# Power_Supply.net
KiCad netlist of a schematic drawn in Altium Designer
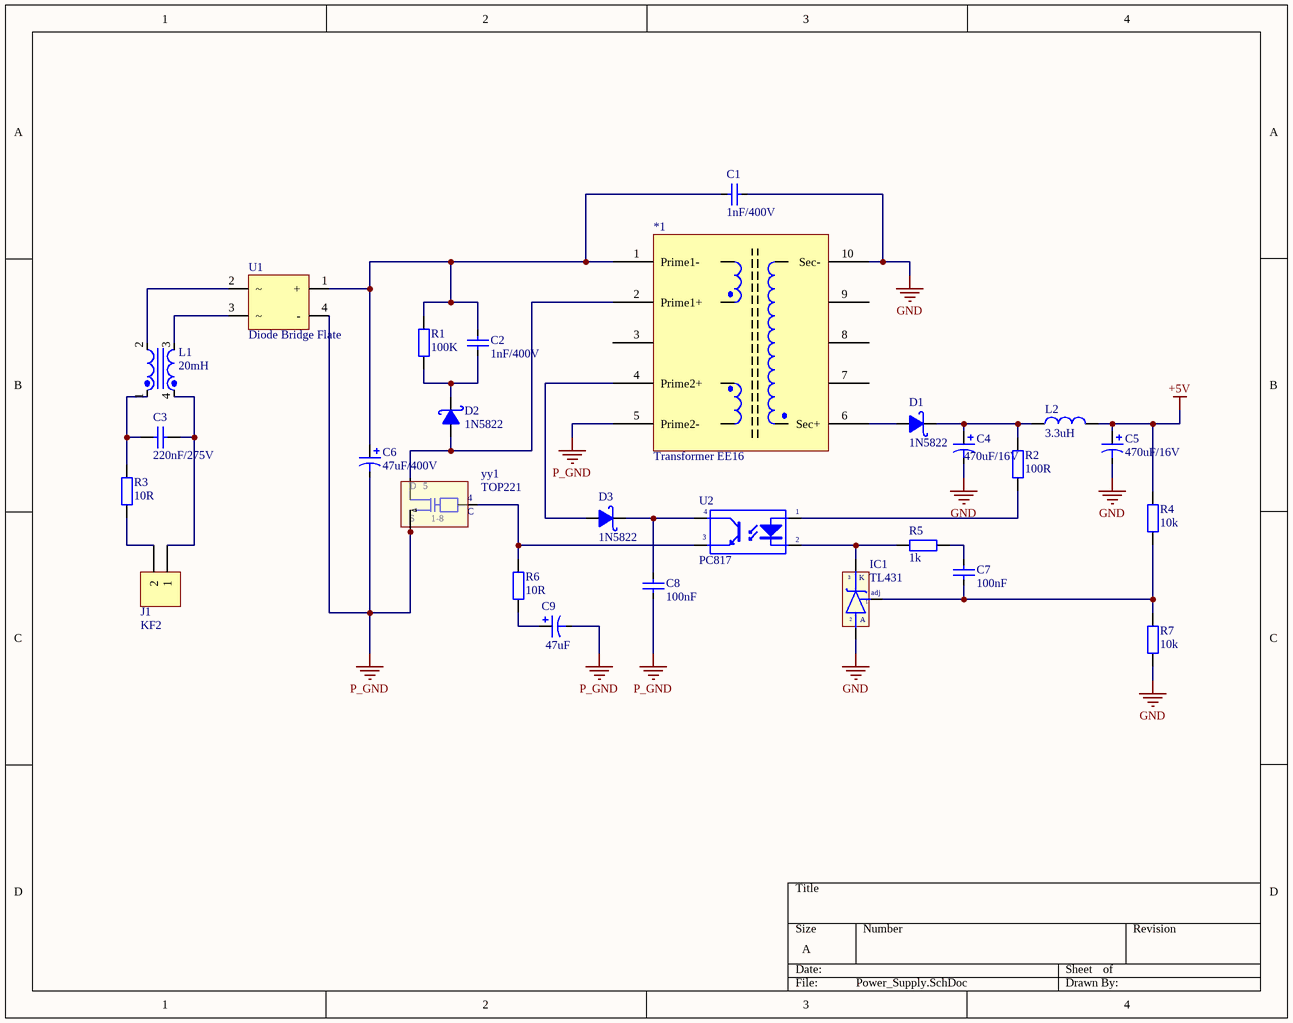
[diagram p0: Power_Supply.SchDoc]

(export (version "E")
  (design (tool "Eeschema 10.0.6"))
  (components
    (comp (ref "*1")
      (value "Transformer EE16")
      (footprint "Transformer SW")
      (libsource (lib "My Library") (part "Transformer EE16"))
    )
    (comp (ref "C1")
      (value "1nF/400V")
      (footprint "103/2KV")
      (description "Capacitor Ceramic 2KV")
      (fields (field (name "PUBLISHER") "Altium Limited"))
      (libsource (lib "My Library") (part "Cap2KV"))
    )
    (comp (ref "C2")
      (value "1nF/400V")
      (footprint "103/2KV")
      (description "Capacitor Ceramic 2KV")
      (fields (field (name "PUBLISHER") "Altium Limited"))
      (libsource (lib "My Library") (part "Cap2KV"))
    )
    (comp (ref "C3")
      (value "220nF/275V")
      (footprint "CN3")
      (description "Capacitor")
      (fields (field (name "Comment") "Capacitor Ceramic") (field (name "PUBLISHER") "Altium Limited"))
      (libsource (lib "My Library") (part "CapCeramic"))
    )
    (comp (ref "C4")
      (value "470uF/16V")
      (footprint "C5mm")
      (description "Polarized Capacitor (Axial)")
      (fields (field (name "PUBLISHER") "Altium Limited"))
      (libsource (lib "My Library") (part "Cap Pol"))
    )
    (comp (ref "C5")
      (value "470uF/16V")
      (footprint "C5mm")
      (description "Polarized Capacitor (Axial)")
      (fields (field (name "PUBLISHER") "Altium Limited"))
      (libsource (lib "My Library") (part "Cap Pol"))
    )
    (comp (ref "C6")
      (value "47uF/400V")
      (footprint "C10mm")
      (description "Polarized Capacitor (Axial)")
      (fields (field (name "PUBLISHER") "Altium Limited"))
      (libsource (lib "My Library") (part "Cap Pol"))
    )
    (comp (ref "C7")
      (value "100nF")
      (footprint "103/2KV")
      (description "Capacitor Ceramic 2KV")
      (fields (field (name "PUBLISHER") "Altium Limited"))
      (libsource (lib "My Library") (part "Cap2KV"))
    )
    (comp (ref "C8")
      (value "100nF")
      (footprint "103/2KV")
      (description "Capacitor Ceramic 2KV")
      (fields (field (name "PUBLISHER") "Altium Limited"))
      (libsource (lib "My Library") (part "Cap2KV"))
    )
    (comp (ref "C9")
      (value "47uF")
      (footprint "C3MM")
      (description "Polarized Capacitor (Axial)")
      (fields (field (name "PUBLISHER") "Altium Limited"))
      (libsource (lib "My Library") (part "Cap Pol"))
    )
    (comp (ref "D1")
      (value "1N5822")
      (footprint "DO-214AC(SMA)")
      (description "Schottky Rectifiers")
      (libsource (lib "My Library") (part "1N5822"))
    )
    (comp (ref "D2")
      (value "1N5822")
      (footprint "DO-214AC(SMA)")
      (description "Schottky Rectifiers")
      (libsource (lib "My Library") (part "1N5822"))
    )
    (comp (ref "D3")
      (value "1N5822")
      (footprint "DO-214AC(SMA)")
      (description "Schottky Rectifiers")
      (libsource (lib "My Library") (part "1N5822"))
    )
    (comp (ref "IC1")
      (value "TL431")
      (footprint "qto-92")
      (description "Programmable Shunt Regulator")
      (libsource (lib "My Library") (part "TL431"))
    )
    (comp (ref "J1")
      (value "KF2")
      (footprint "KF2-5.08")
      (fields
        (field (name "MANUFACTURER") "Würth Elektronik eiSos GmbH")
        (field (name "PARTNO") "691103110002")
        (field (name "CREATED BY") "Karrer Zheng")
      )
      (libsource (lib "My Library") (part "KF2"))
    )
    (comp (ref "L1")
      (value "20mH")
      (footprint "InductorFilter")
      (description "Inductor")
      (fields (field (name "DESIGNED BY") "VanDungEvn"))
      (libsource (lib "My Library") (part "L fiter"))
    )
    (comp (ref "L2")
      (value "3.3uH")
      (footprint "My Library:L-SMD-M-12x10")
      (description "Inductor")
      (libsource (lib "My Library") (part "Inductor"))
    )
    (comp (ref "R1")
      (value "100K")
      (footprint "RES-1WD")
      (description "Resistor SMD")
      (libsource (lib "My Library") (part "RM"))
    )
    (comp (ref "R2")
      (value "100R")
      (footprint "SM-0805")
      (description "Resistor SMD")
      (libsource (lib "My Library") (part "RM"))
    )
    (comp (ref "R3")
      (value "10R")
      (footprint "RES-1WD")
      (description "Resistor SMD")
      (libsource (lib "My Library") (part "RM"))
    )
    (comp (ref "R4")
      (value "10k")
      (footprint "SM-0805")
      (description "Resistor SMD")
      (libsource (lib "My Library") (part "RM"))
    )
    (comp (ref "R5")
      (value "1k")
      (footprint "SM-0805")
      (description "Resistor SMD")
      (libsource (lib "My Library") (part "RM"))
    )
    (comp (ref "R6")
      (value "10R")
      (footprint "SM-0805")
      (description "Resistor SMD")
      (libsource (lib "My Library") (part "RM"))
    )
    (comp (ref "R7")
      (value "10k")
      (footprint "SM-0805")
      (description "Resistor SMD")
      (libsource (lib "My Library") (part "RM"))
    )
    (comp (ref "U1")
      (value "Diode Bridge Flate")
      (footprint "DB207S")
      (description "Diode Bridge")
      (libsource (lib "My Library") (part "Diode Bridge Flate"))
    )
    (comp (ref "U2")
      (value "PC817")
      (footprint "DIP4/W0.3")
      (description "Single Opto")
      (libsource (lib "My Library") (part "PC817"))
    )
    (comp (ref "yy1")
      (value "TOP221")
      (footprint "DIP8/W0.3")
      (description "Family Three-terminal Off-line PWM Switch")
      (libsource (lib "My Library") (part "TOP221-7PG"))
    )
  )
  (nets
    (net (code "1") (name "+5V") (class "Default")
      (node (ref "C5") (pin "1") (pinfunction "1_1") (pintype "passive"))
      (node (ref "L2") (pin "2") (pinfunction "2_2") (pintype "passive"))
      (node (ref "R4") (pin "1") (pinfunction "1_1") (pintype "passive"))
    )
    (net (code "2") (name "GND") (class "Default")
      (node (ref "*1") (pin "10") (pinfunction "Sec-_10") (pintype "passive"))
      (node (ref "C1") (pin "1") (pinfunction "1_1") (pintype "passive"))
      (node (ref "C4") (pin "2") (pinfunction "2_2") (pintype "passive"))
      (node (ref "C5") (pin "2") (pinfunction "2_2") (pintype "passive"))
      (node (ref "IC1") (pin "2") (pinfunction "A_2") (pintype "passive"))
      (node (ref "R7") (pin "2") (pinfunction "2_2") (pintype "passive"))
    )
    (net (code "3") (name "Net-(*1-Prime1+)") (class "Default")
      (node (ref "*1") (pin "2") (pinfunction "Prime1+_2") (pintype "passive"))
      (node (ref "D2") (pin "1") (pinfunction "A_1") (pintype "passive"))
      (node (ref "yy1") (pin "5") (pinfunction "D_5") (pintype "passive"))
    )
    (net (code "4") (name "Net-(*1-Prime1-)") (class "Default")
      (node (ref "*1") (pin "1") (pinfunction "Prime1-_1") (pintype "passive"))
      (node (ref "C1") (pin "2") (pinfunction "2_2") (pintype "passive"))
      (node (ref "C2") (pin "2") (pinfunction "2_2") (pintype "passive"))
      (node (ref "C6") (pin "1") (pinfunction "1_1") (pintype "passive"))
      (node (ref "R1") (pin "2") (pinfunction "2_2") (pintype "passive"))
      (node (ref "U1") (pin "1") (pinfunction "+_1") (pintype "passive"))
    )
    (net (code "5") (name "Net-(*1-Prime2+)") (class "Default")
      (node (ref "*1") (pin "4") (pinfunction "Prime2+_4") (pintype "passive"))
      (node (ref "D3") (pin "1") (pinfunction "A_1") (pintype "passive"))
    )
    (net (code "6") (name "Net-(*1-Sec+)") (class "Default")
      (node (ref "*1") (pin "6") (pinfunction "Sec+_6") (pintype "passive"))
      (node (ref "D1") (pin "1") (pinfunction "A_1") (pintype "passive"))
    )
    (net (code "7") (name "Net-(C3-Pad1)") (class "Default")
      (node (ref "C3") (pin "1") (pinfunction "1_1") (pintype "passive"))
      (node (ref "L1") (pin "1") (pintype "passive"))
      (node (ref "R3") (pin "2") (pinfunction "2_2") (pintype "passive"))
    )
    (net (code "8") (name "Net-(C3-Pad2)") (class "Default")
      (node (ref "C3") (pin "2") (pinfunction "2_2") (pintype "passive"))
      (node (ref "J1") (pin "1") (pinfunction "1_1") (pintype "passive"))
      (node (ref "L1") (pin "4") (pintype "passive"))
    )
    (net (code "9") (name "Net-(C7-Pad2)") (class "Default")
      (node (ref "C7") (pin "2") (pinfunction "2_2") (pintype "passive"))
      (node (ref "R5") (pin "1") (pinfunction "1_1") (pintype "passive"))
    )
    (net (code "10") (name "Net-(C9-Pad1)") (class "Default")
      (node (ref "C9") (pin "1") (pinfunction "1_1") (pintype "passive"))
      (node (ref "R6") (pin "1") (pinfunction "1_1") (pintype "passive"))
    )
    (net (code "11") (name "Net-(D1-K)") (class "Default")
      (node (ref "C4") (pin "1") (pinfunction "1_1") (pintype "passive"))
      (node (ref "D1") (pin "2") (pinfunction "K_2") (pintype "passive"))
      (node (ref "L2") (pin "1") (pinfunction "1_1") (pintype "passive"))
      (node (ref "R2") (pin "2") (pinfunction "2_2") (pintype "passive"))
    )
    (net (code "12") (name "Net-(D2-K)") (class "Default")
      (node (ref "C2") (pin "1") (pinfunction "1_1") (pintype "passive"))
      (node (ref "D2") (pin "2") (pinfunction "K_2") (pintype "passive"))
      (node (ref "R1") (pin "1") (pinfunction "1_1") (pintype "passive"))
    )
    (net (code "13") (name "Net-(D3-K)") (class "Default")
      (node (ref "C8") (pin "2") (pinfunction "2_2") (pintype "passive"))
      (node (ref "D3") (pin "2") (pinfunction "K_2") (pintype "passive"))
      (node (ref "U2") (pin "4") (pinfunction "C_4") (pintype "passive"))
    )
    (net (code "14") (name "Net-(IC1-K)") (class "Default")
      (node (ref "IC1") (pin "3") (pinfunction "K_3") (pintype "passive"))
      (node (ref "R5") (pin "2") (pinfunction "2_2") (pintype "passive"))
      (node (ref "U2") (pin "2") (pinfunction "K_2") (pintype "passive"))
    )
    (net (code "15") (name "Net-(IC1-adj)") (class "Default")
      (node (ref "C7") (pin "1") (pinfunction "1_1") (pintype "passive"))
      (node (ref "IC1") (pin "1") (pinfunction "adj_1") (pintype "passive"))
      (node (ref "R4") (pin "2") (pinfunction "2_2") (pintype "passive"))
      (node (ref "R7") (pin "1") (pinfunction "1_1") (pintype "passive"))
    )
    (net (code "16") (name "Net-(J1-Pad2)") (class "Default")
      (node (ref "J1") (pin "2") (pinfunction "2_2") (pintype "passive"))
      (node (ref "R3") (pin "1") (pinfunction "1_1") (pintype "passive"))
    )
    (net (code "17") (name "Net-(L1-Pad2)") (class "Default")
      (node (ref "L1") (pin "2") (pintype "passive"))
      (node (ref "U1") (pin "2") (pinfunction "~_2") (pintype "passive"))
    )
    (net (code "18") (name "Net-(L1-Pad3)") (class "Default")
      (node (ref "L1") (pin "3") (pintype "passive"))
      (node (ref "U1") (pin "3") (pinfunction "~_3") (pintype "passive"))
    )
    (net (code "19") (name "Net-(U2-A)") (class "Default")
      (node (ref "R2") (pin "1") (pinfunction "1_1") (pintype "passive"))
      (node (ref "U2") (pin "1") (pinfunction "A_1") (pintype "passive"))
    )
    (net (code "20") (name "Net-(U2-E)") (class "Default")
      (node (ref "R6") (pin "2") (pinfunction "2_2") (pintype "passive"))
      (node (ref "U2") (pin "3") (pinfunction "E_3") (pintype "passive"))
      (node (ref "yy1") (pin "4") (pinfunction "C_4") (pintype "passive"))
    )
    (net (code "21") (name "P_GND") (class "Default")
      (node (ref "*1") (pin "5") (pinfunction "Prime2-_5") (pintype "passive"))
      (node (ref "C6") (pin "2") (pinfunction "2_2") (pintype "passive"))
      (node (ref "C8") (pin "1") (pinfunction "1_1") (pintype "passive"))
      (node (ref "C9") (pin "2") (pinfunction "2_2") (pintype "passive"))
      (node (ref "U1") (pin "4") (pinfunction "-_4") (pintype "passive"))
      (node (ref "yy1") (pin "1") (pinfunction "S_1") (pintype "passive"))
      (node (ref "yy1") (pin "2") (pinfunction "S_2") (pintype "passive"))
      (node (ref "yy1") (pin "3") (pinfunction "S_3") (pintype "passive"))
      (node (ref "yy1") (pin "6") (pinfunction "S_6") (pintype "passive"))
      (node (ref "yy1") (pin "7") (pinfunction "S_7") (pintype "passive"))
      (node (ref "yy1") (pin "8") (pinfunction "S_8") (pintype "passive"))
    )
    (net (code "22") (name "unconnected-(*1-Pad3)") (class "Default")
      (node (ref "*1") (pin "3") (pintype "passive"))
    )
    (net (code "23") (name "unconnected-(*1-Pad7)") (class "Default")
      (node (ref "*1") (pin "7") (pintype "passive"))
    )
    (net (code "24") (name "unconnected-(*1-Pad8)") (class "Default")
      (node (ref "*1") (pin "8") (pintype "passive"))
    )
    (net (code "25") (name "unconnected-(*1-Pad9)") (class "Default")
      (node (ref "*1") (pin "9") (pintype "passive"))
    )
  )
)
